# MIDI-Patchbay-Shield.net
KiCad netlist of a schematic drawn in EAGLE
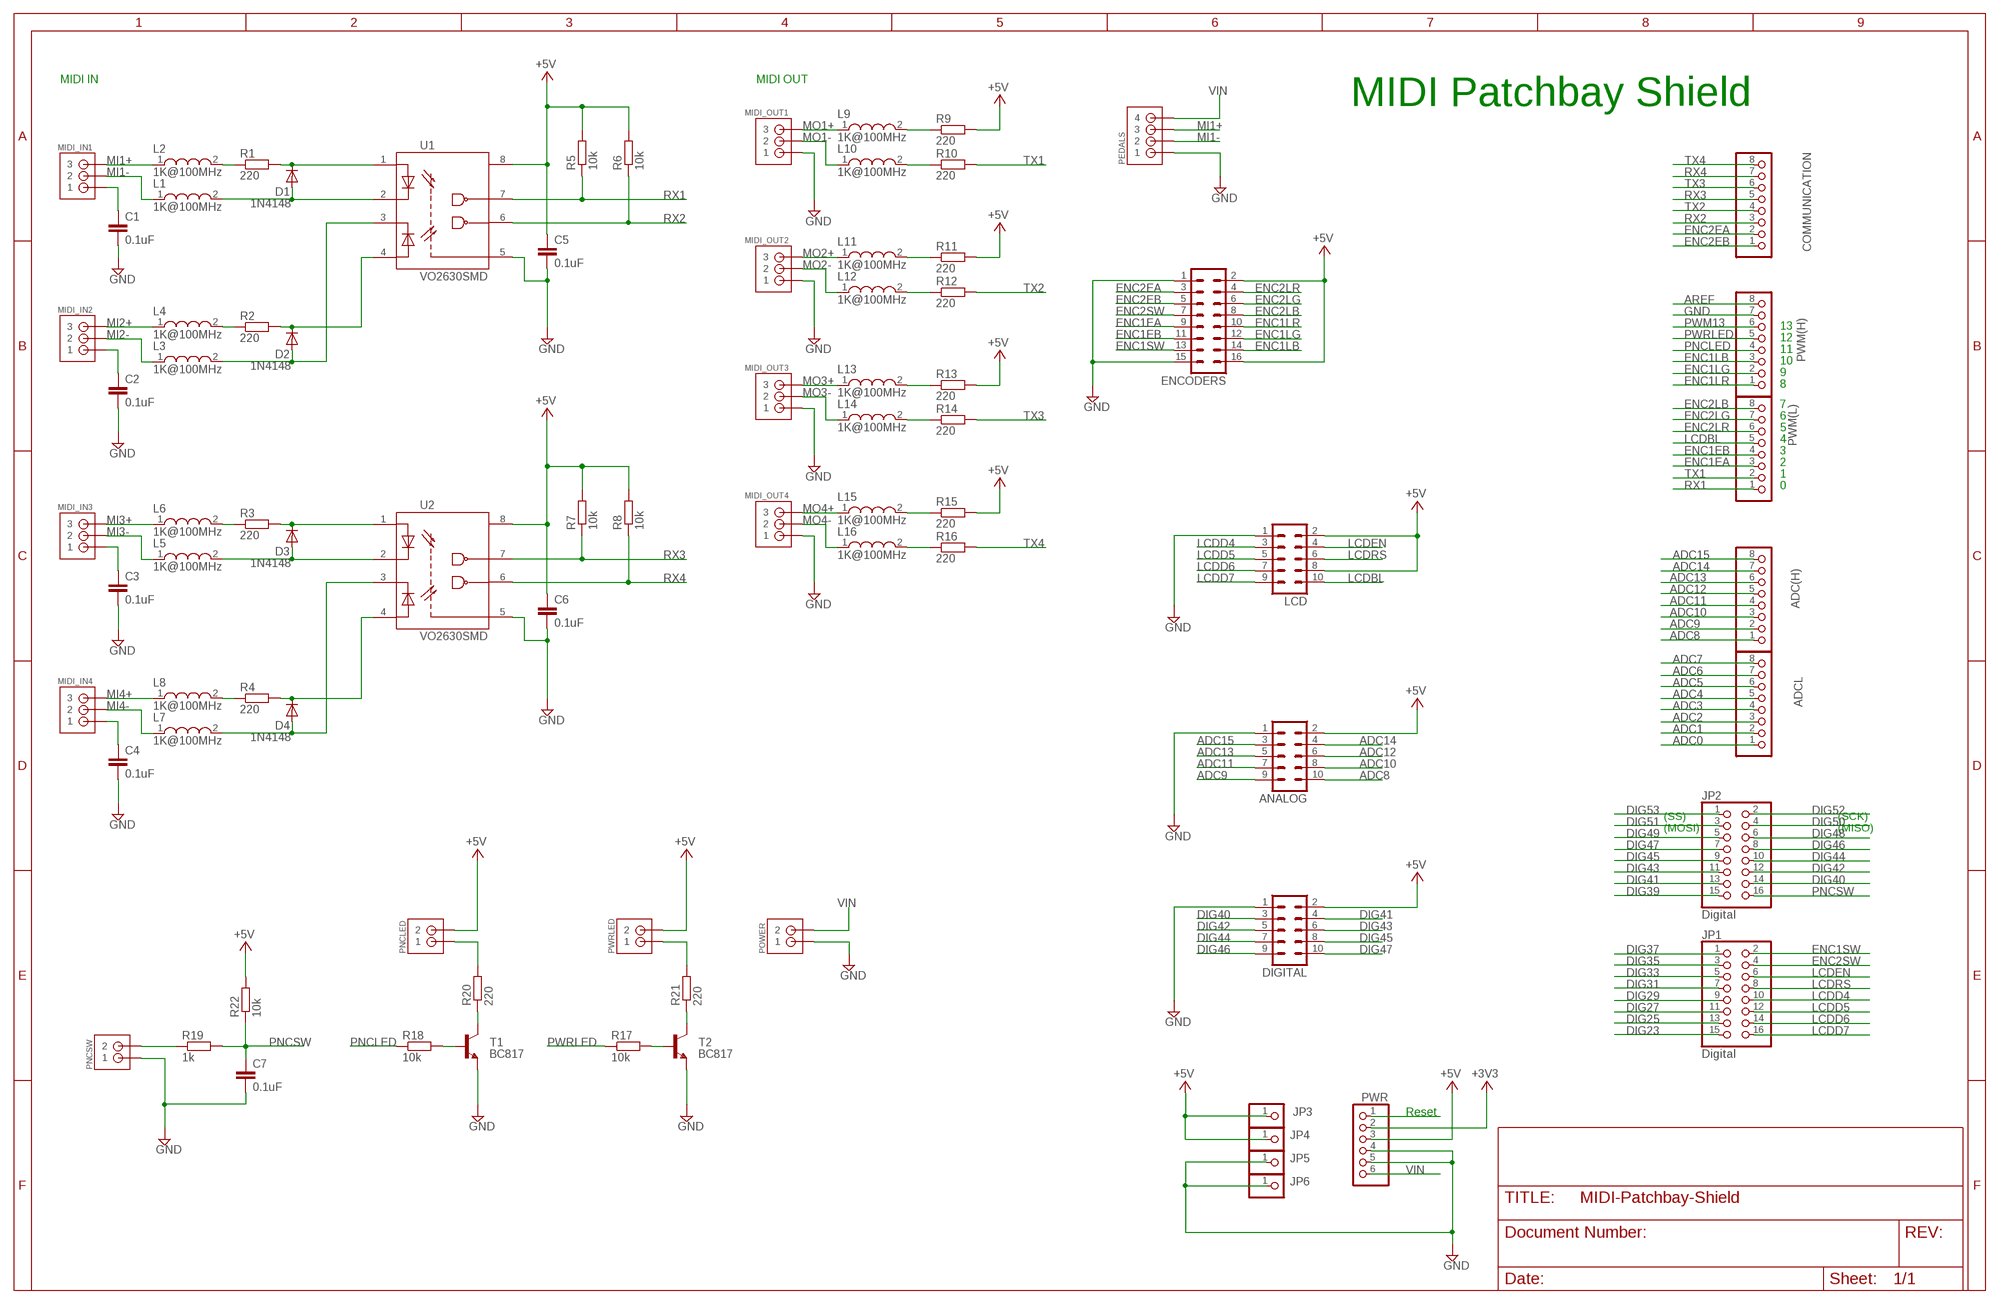
[diagram p0: schematic, sheet 1]

(export (version "E")
  (design (tool "Eeschema 10.0.6"))
  (components
    (comp (ref "ADC(H)")
      (value "PINHD-1X8")
      (footprint "eagle-import:1X08")
      (libsource (lib "eagle-import") (part "PINHD-1X8"))
    )
    (comp (ref "ADCL")
      (value "PINHD-1X8")
      (footprint "eagle-import:1X08")
      (libsource (lib "eagle-import") (part "PINHD-1X8"))
    )
    (comp (ref "ANALOG")
      (value "ML10")
      (footprint "eagle-import:ML10")
      (libsource (lib "eagle-import") (part "ML10"))
    )
    (comp (ref "C1")
      (value "0.1uF")
      (footprint "eagle-import:0805")
      (libsource (lib "eagle-import") (part "CAP0805"))
    )
    (comp (ref "C2")
      (value "0.1uF")
      (footprint "eagle-import:0805")
      (libsource (lib "eagle-import") (part "CAP0805"))
    )
    (comp (ref "C3")
      (value "0.1uF")
      (footprint "eagle-import:0805")
      (libsource (lib "eagle-import") (part "CAP0805"))
    )
    (comp (ref "C4")
      (value "0.1uF")
      (footprint "eagle-import:0805")
      (libsource (lib "eagle-import") (part "CAP0805"))
    )
    (comp (ref "C5")
      (value "0.1uF")
      (footprint "eagle-import:C0805")
      (libsource (lib "eagle-import") (part "C-EUC0805"))
    )
    (comp (ref "C6")
      (value "0.1uF")
      (footprint "eagle-import:C0805")
      (libsource (lib "eagle-import") (part "C-EUC0805"))
    )
    (comp (ref "C7")
      (value "0.1uF")
      (footprint "eagle-import:0805")
      (libsource (lib "eagle-import") (part "CAP0805"))
    )
    (comp (ref "COMMUNICATION")
      (value "PINHD-1X8")
      (footprint "eagle-import:1X08")
      (libsource (lib "eagle-import") (part "PINHD-1X8"))
    )
    (comp (ref "D1")
      (value "1N4148")
      (footprint "eagle-import:SOD323-W")
      (libsource (lib "eagle-import") (part "1N4148"))
    )
    (comp (ref "D2")
      (value "1N4148")
      (footprint "eagle-import:SOD323-W")
      (libsource (lib "eagle-import") (part "1N4148"))
    )
    (comp (ref "D3")
      (value "1N4148")
      (footprint "eagle-import:SOD323-W")
      (libsource (lib "eagle-import") (part "1N4148"))
    )
    (comp (ref "D4")
      (value "1N4148")
      (footprint "eagle-import:SOD323-W")
      (libsource (lib "eagle-import") (part "1N4148"))
    )
    (comp (ref "DIGITAL")
      (value "ML10")
      (footprint "eagle-import:ML10")
      (libsource (lib "eagle-import") (part "ML10"))
    )
    (comp (ref "ENCODERS")
      (value "ML16")
      (footprint "eagle-import:ML16")
      (libsource (lib "eagle-import") (part "ML16"))
    )
    (comp (ref "JP1")
      (value "Digital")
      (footprint "eagle-import:2X08")
      (libsource (lib "eagle-import") (part "PINHD-2X8"))
    )
    (comp (ref "JP2")
      (value "Digital")
      (footprint "eagle-import:2X08")
      (libsource (lib "eagle-import") (part "PINHD-2X8"))
    )
    (comp (ref "JP3")
      (value "PINHD-1X1")
      (footprint "eagle-import:1X01")
      (libsource (lib "eagle-import") (part "PINHD-1X1"))
    )
    (comp (ref "JP4")
      (value "PINHD-1X1")
      (footprint "eagle-import:1X01")
      (libsource (lib "eagle-import") (part "PINHD-1X1"))
    )
    (comp (ref "JP5")
      (value "PINHD-1X1")
      (footprint "eagle-import:1X01")
      (libsource (lib "eagle-import") (part "PINHD-1X1"))
    )
    (comp (ref "JP6")
      (value "PINHD-1X1")
      (footprint "eagle-import:1X01")
      (libsource (lib "eagle-import") (part "PINHD-1X1"))
    )
    (comp (ref "L1")
      (value "1K@100MHz")
      (footprint "eagle-import:WE-RFI_0805")
      (libsource (lib "eagle-import") (part "WE-RFI_0805"))
    )
    (comp (ref "L2")
      (value "1K@100MHz")
      (footprint "eagle-import:WE-RFI_0805")
      (libsource (lib "eagle-import") (part "WE-RFI_0805"))
    )
    (comp (ref "L3")
      (value "1K@100MHz")
      (footprint "eagle-import:WE-RFI_0805")
      (libsource (lib "eagle-import") (part "WE-RFI_0805"))
    )
    (comp (ref "L4")
      (value "1K@100MHz")
      (footprint "eagle-import:WE-RFI_0805")
      (libsource (lib "eagle-import") (part "WE-RFI_0805"))
    )
    (comp (ref "L5")
      (value "1K@100MHz")
      (footprint "eagle-import:WE-RFI_0805")
      (libsource (lib "eagle-import") (part "WE-RFI_0805"))
    )
    (comp (ref "L6")
      (value "1K@100MHz")
      (footprint "eagle-import:WE-RFI_0805")
      (libsource (lib "eagle-import") (part "WE-RFI_0805"))
    )
    (comp (ref "L7")
      (value "1K@100MHz")
      (footprint "eagle-import:WE-RFI_0805")
      (libsource (lib "eagle-import") (part "WE-RFI_0805"))
    )
    (comp (ref "L8")
      (value "1K@100MHz")
      (footprint "eagle-import:WE-RFI_0805")
      (libsource (lib "eagle-import") (part "WE-RFI_0805"))
    )
    (comp (ref "L9")
      (value "1K@100MHz")
      (footprint "eagle-import:WE-RFI_0805")
      (libsource (lib "eagle-import") (part "WE-RFI_0805"))
    )
    (comp (ref "L10")
      (value "1K@100MHz")
      (footprint "eagle-import:WE-RFI_0805")
      (libsource (lib "eagle-import") (part "WE-RFI_0805"))
    )
    (comp (ref "L11")
      (value "1K@100MHz")
      (footprint "eagle-import:WE-RFI_0805")
      (libsource (lib "eagle-import") (part "WE-RFI_0805"))
    )
    (comp (ref "L12")
      (value "1K@100MHz")
      (footprint "eagle-import:WE-RFI_0805")
      (libsource (lib "eagle-import") (part "WE-RFI_0805"))
    )
    (comp (ref "L13")
      (value "1K@100MHz")
      (footprint "eagle-import:WE-RFI_0805")
      (libsource (lib "eagle-import") (part "WE-RFI_0805"))
    )
    (comp (ref "L14")
      (value "1K@100MHz")
      (footprint "eagle-import:WE-RFI_0805")
      (libsource (lib "eagle-import") (part "WE-RFI_0805"))
    )
    (comp (ref "L15")
      (value "1K@100MHz")
      (footprint "eagle-import:WE-RFI_0805")
      (libsource (lib "eagle-import") (part "WE-RFI_0805"))
    )
    (comp (ref "L16")
      (value "1K@100MHz")
      (footprint "eagle-import:WE-RFI_0805")
      (libsource (lib "eagle-import") (part "WE-RFI_0805"))
    )
    (comp (ref "LCD")
      (value "ML10")
      (footprint "eagle-import:ML10")
      (libsource (lib "eagle-import") (part "ML10"))
    )
    (comp (ref "MIDI_IN1")
      (value "JST-XA-03-PIN")
      (footprint "eagle-import:JST-XA-03")
      (libsource (lib "eagle-import") (part "JST-XA-03-PIN"))
    )
    (comp (ref "MIDI_IN2")
      (value "JST-XA-03-PIN")
      (footprint "eagle-import:JST-XA-03")
      (libsource (lib "eagle-import") (part "JST-XA-03-PIN"))
    )
    (comp (ref "MIDI_IN3")
      (value "JST-XA-03-PIN")
      (footprint "eagle-import:JST-XA-03")
      (libsource (lib "eagle-import") (part "JST-XA-03-PIN"))
    )
    (comp (ref "MIDI_IN4")
      (value "JST-XA-03-PIN")
      (footprint "eagle-import:JST-XA-03")
      (libsource (lib "eagle-import") (part "JST-XA-03-PIN"))
    )
    (comp (ref "MIDI_OUT1")
      (value "JST-XA-03-PIN")
      (footprint "eagle-import:JST-XA-03")
      (libsource (lib "eagle-import") (part "JST-XA-03-PIN"))
    )
    (comp (ref "MIDI_OUT2")
      (value "JST-XA-03-PIN")
      (footprint "eagle-import:JST-XA-03")
      (libsource (lib "eagle-import") (part "JST-XA-03-PIN"))
    )
    (comp (ref "MIDI_OUT3")
      (value "JST-XA-03-PIN")
      (footprint "eagle-import:JST-XA-03")
      (libsource (lib "eagle-import") (part "JST-XA-03-PIN"))
    )
    (comp (ref "MIDI_OUT4")
      (value "JST-XA-03-PIN")
      (footprint "eagle-import:JST-XA-03")
      (libsource (lib "eagle-import") (part "JST-XA-03-PIN"))
    )
    (comp (ref "PEDALS")
      (value "JST-XA-04-PIN")
      (footprint "eagle-import:JST-XA-04")
      (libsource (lib "eagle-import") (part "JST-XA-04-PIN"))
    )
    (comp (ref "PNCLED")
      (value "JST-XA-02-PIN")
      (footprint "eagle-import:JST-XA-02")
      (libsource (lib "eagle-import") (part "JST-XA-02-PIN"))
    )
    (comp (ref "PNCSW")
      (value "JST-XA-02-PIN")
      (footprint "eagle-import:JST-XA-02")
      (libsource (lib "eagle-import") (part "JST-XA-02-PIN"))
    )
    (comp (ref "POWER")
      (value "JST-XA-02-PIN")
      (footprint "eagle-import:JST-XA-02")
      (libsource (lib "eagle-import") (part "JST-XA-02-PIN"))
    )
    (comp (ref "PWM(H)")
      (value "PINHD-1X8")
      (footprint "eagle-import:1X08")
      (libsource (lib "eagle-import") (part "PINHD-1X8"))
    )
    (comp (ref "PWM(L)")
      (value "PINHD-1X8")
      (footprint "eagle-import:1X08")
      (libsource (lib "eagle-import") (part "PINHD-1X8"))
    )
    (comp (ref "PWR")
      (value "PINHD-1X6")
      (footprint "eagle-import:1X06")
      (libsource (lib "eagle-import") (part "PINHD-1X6"))
    )
    (comp (ref "PWRLED")
      (value "JST-XA-02-PIN")
      (footprint "eagle-import:JST-XA-02")
      (libsource (lib "eagle-import") (part "JST-XA-02-PIN"))
    )
    (comp (ref "R1")
      (value "220")
      (footprint "eagle-import:M0805")
      (libsource (lib "eagle-import") (part "R-EU_M0805"))
    )
    (comp (ref "R2")
      (value "220")
      (footprint "eagle-import:M0805")
      (libsource (lib "eagle-import") (part "R-EU_M0805"))
    )
    (comp (ref "R3")
      (value "220")
      (footprint "eagle-import:M0805")
      (libsource (lib "eagle-import") (part "R-EU_M0805"))
    )
    (comp (ref "R4")
      (value "220")
      (footprint "eagle-import:M0805")
      (libsource (lib "eagle-import") (part "R-EU_M0805"))
    )
    (comp (ref "R5")
      (value "10k")
      (footprint "eagle-import:R0805")
      (libsource (lib "eagle-import") (part "R-EU_R0805"))
    )
    (comp (ref "R6")
      (value "10k")
      (footprint "eagle-import:R0805")
      (libsource (lib "eagle-import") (part "R-EU_R0805"))
    )
    (comp (ref "R7")
      (value "10k")
      (footprint "eagle-import:R0805")
      (libsource (lib "eagle-import") (part "R-EU_R0805"))
    )
    (comp (ref "R8")
      (value "10k")
      (footprint "eagle-import:R0805")
      (libsource (lib "eagle-import") (part "R-EU_R0805"))
    )
    (comp (ref "R9")
      (value "220")
      (footprint "eagle-import:M0805")
      (libsource (lib "eagle-import") (part "R-EU_M0805"))
    )
    (comp (ref "R10")
      (value "220")
      (footprint "eagle-import:M0805")
      (libsource (lib "eagle-import") (part "R-EU_M0805"))
    )
    (comp (ref "R11")
      (value "220")
      (footprint "eagle-import:M0805")
      (libsource (lib "eagle-import") (part "R-EU_M0805"))
    )
    (comp (ref "R12")
      (value "220")
      (footprint "eagle-import:M0805")
      (libsource (lib "eagle-import") (part "R-EU_M0805"))
    )
    (comp (ref "R13")
      (value "220")
      (footprint "eagle-import:M0805")
      (libsource (lib "eagle-import") (part "R-EU_M0805"))
    )
    (comp (ref "R14")
      (value "220")
      (footprint "eagle-import:M0805")
      (libsource (lib "eagle-import") (part "R-EU_M0805"))
    )
    (comp (ref "R15")
      (value "220")
      (footprint "eagle-import:M0805")
      (libsource (lib "eagle-import") (part "R-EU_M0805"))
    )
    (comp (ref "R16")
      (value "220")
      (footprint "eagle-import:M0805")
      (libsource (lib "eagle-import") (part "R-EU_M0805"))
    )
    (comp (ref "R17")
      (value "10k")
      (footprint "eagle-import:R0805")
      (fields (field (name "SPICEPREFIX") "R"))
      (libsource (lib "eagle-import") (part "R-EU_R0805"))
    )
    (comp (ref "R18")
      (value "10k")
      (footprint "eagle-import:R0805")
      (fields (field (name "SPICEPREFIX") "R"))
      (libsource (lib "eagle-import") (part "R-EU_R0805"))
    )
    (comp (ref "R19")
      (value "1k")
      (footprint "eagle-import:R0805")
      (fields (field (name "SPICEPREFIX") "R"))
      (libsource (lib "eagle-import") (part "R-EU_R0805"))
    )
    (comp (ref "R20")
      (value "220")
      (footprint "eagle-import:M0805")
      (libsource (lib "eagle-import") (part "R-EU_M0805"))
    )
    (comp (ref "R21")
      (value "220")
      (footprint "eagle-import:M0805")
      (libsource (lib "eagle-import") (part "R-EU_M0805"))
    )
    (comp (ref "R22")
      (value "10k")
      (footprint "eagle-import:R0805")
      (fields (field (name "SPICEPREFIX") "R"))
      (libsource (lib "eagle-import") (part "R-EU_R0805"))
    )
    (comp (ref "T1")
      (value "BC817")
      (footprint "eagle-import:SOT23")
      (libsource (lib "eagle-import") (part "BC817"))
    )
    (comp (ref "T2")
      (value "BC817")
      (footprint "eagle-import:SOT23")
      (libsource (lib "eagle-import") (part "BC817"))
    )
    (comp (ref "U1")
      (value "VO2630SMD")
      (footprint "eagle-import:SOIC254P1030X390-8N")
      (libsource (lib "eagle-import") (part "VO2630SMD"))
    )
    (comp (ref "U2")
      (value "VO2630SMD")
      (footprint "eagle-import:SOIC254P1030X390-8N")
      (libsource (lib "eagle-import") (part "VO2630SMD"))
    )
  )
  (nets
    (net (code "1") (name "+3V3") (class "Default")
      (node (ref "PWR") (pin "2") (pinfunction "2_2") (pintype "passive"))
    )
    (net (code "2") (name "+5V") (class "Default")
      (node (ref "ANALOG") (pin "2") (pinfunction "2_2") (pintype "passive"))
      (node (ref "C5") (pin "1") (pinfunction "1_1") (pintype "passive"))
      (node (ref "C6") (pin "1") (pinfunction "1_1") (pintype "passive"))
      (node (ref "DIGITAL") (pin "2") (pinfunction "2_2") (pintype "passive"))
      (node (ref "ENCODERS") (pin "16") (pinfunction "16_16") (pintype "passive"))
      (node (ref "ENCODERS") (pin "2") (pinfunction "2_2") (pintype "passive"))
      (node (ref "JP3") (pin "1") (pinfunction "1_1") (pintype "passive"))
      (node (ref "JP4") (pin "1") (pinfunction "1_1") (pintype "passive"))
      (node (ref "LCD") (pin "2") (pinfunction "2_2") (pintype "passive"))
      (node (ref "LCD") (pin "8") (pinfunction "8_8") (pintype "passive"))
      (node (ref "PNCLED") (pin "2") (pinfunction "2_2") (pintype "bidirectional"))
      (node (ref "PWR") (pin "3") (pinfunction "3_3") (pintype "passive"))
      (node (ref "PWRLED") (pin "2") (pinfunction "2_2") (pintype "bidirectional"))
      (node (ref "R11") (pin "2") (pinfunction "2_2") (pintype "passive"))
      (node (ref "R13") (pin "2") (pinfunction "2_2") (pintype "passive"))
      (node (ref "R15") (pin "2") (pinfunction "2_2") (pintype "passive"))
      (node (ref "R22") (pin "2") (pinfunction "2_2") (pintype "passive"))
      (node (ref "R5") (pin "2") (pinfunction "2_2") (pintype "passive"))
      (node (ref "R6") (pin "2") (pinfunction "2_2") (pintype "passive"))
      (node (ref "R7") (pin "2") (pinfunction "2_2") (pintype "passive"))
      (node (ref "R8") (pin "2") (pinfunction "2_2") (pintype "passive"))
      (node (ref "R9") (pin "2") (pinfunction "2_2") (pintype "passive"))
      (node (ref "U1") (pin "8") (pinfunction "VCC_8") (pintype "power_in"))
      (node (ref "U2") (pin "8") (pinfunction "VCC_8") (pintype "power_in"))
    )
    (net (code "3") (name "/ADC0") (class "Default")
      (node (ref "ADCL") (pin "1") (pinfunction "1_1") (pintype "passive"))
    )
    (net (code "4") (name "/ADC1") (class "Default")
      (node (ref "ADCL") (pin "2") (pinfunction "2_2") (pintype "passive"))
    )
    (net (code "5") (name "/ADC2") (class "Default")
      (node (ref "ADCL") (pin "3") (pinfunction "3_3") (pintype "passive"))
    )
    (net (code "6") (name "/ADC3") (class "Default")
      (node (ref "ADCL") (pin "4") (pinfunction "4_4") (pintype "passive"))
    )
    (net (code "7") (name "/ADC4") (class "Default")
      (node (ref "ADCL") (pin "5") (pinfunction "5_5") (pintype "passive"))
    )
    (net (code "8") (name "/ADC5") (class "Default")
      (node (ref "ADCL") (pin "6") (pinfunction "6_6") (pintype "passive"))
    )
    (net (code "9") (name "/ADC6") (class "Default")
      (node (ref "ADCL") (pin "7") (pinfunction "7_7") (pintype "passive"))
    )
    (net (code "10") (name "/ADC7") (class "Default")
      (node (ref "ADCL") (pin "8") (pinfunction "8_8") (pintype "passive"))
    )
    (net (code "11") (name "/ADC8") (class "Default")
      (node (ref "ADC(H)") (pin "1") (pinfunction "1_1") (pintype "passive"))
      (node (ref "ANALOG") (pin "10") (pinfunction "10_10") (pintype "passive"))
    )
    (net (code "12") (name "/ADC9") (class "Default")
      (node (ref "ADC(H)") (pin "2") (pinfunction "2_2") (pintype "passive"))
      (node (ref "ANALOG") (pin "9") (pinfunction "9_9") (pintype "passive"))
    )
    (net (code "13") (name "/ADC10") (class "Default")
      (node (ref "ADC(H)") (pin "3") (pinfunction "3_3") (pintype "passive"))
      (node (ref "ANALOG") (pin "8") (pinfunction "8_8") (pintype "passive"))
    )
    (net (code "14") (name "/ADC11") (class "Default")
      (node (ref "ADC(H)") (pin "4") (pinfunction "4_4") (pintype "passive"))
      (node (ref "ANALOG") (pin "7") (pinfunction "7_7") (pintype "passive"))
    )
    (net (code "15") (name "/ADC12") (class "Default")
      (node (ref "ADC(H)") (pin "5") (pinfunction "5_5") (pintype "passive"))
      (node (ref "ANALOG") (pin "6") (pinfunction "6_6") (pintype "passive"))
    )
    (net (code "16") (name "/ADC13") (class "Default")
      (node (ref "ADC(H)") (pin "6") (pinfunction "6_6") (pintype "passive"))
      (node (ref "ANALOG") (pin "5") (pinfunction "5_5") (pintype "passive"))
    )
    (net (code "17") (name "/ADC14") (class "Default")
      (node (ref "ADC(H)") (pin "7") (pinfunction "7_7") (pintype "passive"))
      (node (ref "ANALOG") (pin "4") (pinfunction "4_4") (pintype "passive"))
    )
    (net (code "18") (name "/ADC15") (class "Default")
      (node (ref "ADC(H)") (pin "8") (pinfunction "8_8") (pintype "passive"))
      (node (ref "ANALOG") (pin "3") (pinfunction "3_3") (pintype "passive"))
    )
    (net (code "19") (name "/AREF") (class "Default")
      (node (ref "PWM(H)") (pin "8") (pinfunction "8_8") (pintype "passive"))
    )
    (net (code "20") (name "/DIG23") (class "Default")
      (node (ref "JP1") (pin "15") (pinfunction "15_15") (pintype "passive"))
    )
    (net (code "21") (name "/DIG25") (class "Default")
      (node (ref "JP1") (pin "13") (pinfunction "13_13") (pintype "passive"))
    )
    (net (code "22") (name "/DIG27") (class "Default")
      (node (ref "JP1") (pin "11") (pinfunction "11_11") (pintype "passive"))
    )
    (net (code "23") (name "/DIG29") (class "Default")
      (node (ref "JP1") (pin "9") (pinfunction "9_9") (pintype "passive"))
    )
    (net (code "24") (name "/DIG31") (class "Default")
      (node (ref "JP1") (pin "7") (pinfunction "7_7") (pintype "passive"))
    )
    (net (code "25") (name "/DIG33") (class "Default")
      (node (ref "JP1") (pin "5") (pinfunction "5_5") (pintype "passive"))
    )
    (net (code "26") (name "/DIG35") (class "Default")
      (node (ref "JP1") (pin "3") (pinfunction "3_3") (pintype "passive"))
    )
    (net (code "27") (name "/DIG37") (class "Default")
      (node (ref "JP1") (pin "1") (pinfunction "1_1") (pintype "passive"))
    )
    (net (code "28") (name "/DIG39") (class "Default")
      (node (ref "JP2") (pin "15") (pinfunction "15_15") (pintype "passive"))
    )
    (net (code "29") (name "/DIG40") (class "Default")
      (node (ref "DIGITAL") (pin "3") (pinfunction "3_3") (pintype "passive"))
      (node (ref "JP2") (pin "14") (pinfunction "14_14") (pintype "passive"))
    )
    (net (code "30") (name "/DIG41") (class "Default")
      (node (ref "DIGITAL") (pin "4") (pinfunction "4_4") (pintype "passive"))
      (node (ref "JP2") (pin "13") (pinfunction "13_13") (pintype "passive"))
    )
    (net (code "31") (name "/DIG42") (class "Default")
      (node (ref "DIGITAL") (pin "5") (pinfunction "5_5") (pintype "passive"))
      (node (ref "JP2") (pin "12") (pinfunction "12_12") (pintype "passive"))
    )
    (net (code "32") (name "/DIG43") (class "Default")
      (node (ref "DIGITAL") (pin "6") (pinfunction "6_6") (pintype "passive"))
      (node (ref "JP2") (pin "11") (pinfunction "11_11") (pintype "passive"))
    )
    (net (code "33") (name "/DIG44") (class "Default")
      (node (ref "DIGITAL") (pin "7") (pinfunction "7_7") (pintype "passive"))
      (node (ref "JP2") (pin "10") (pinfunction "10_10") (pintype "passive"))
    )
    (net (code "34") (name "/DIG45") (class "Default")
      (node (ref "DIGITAL") (pin "8") (pinfunction "8_8") (pintype "passive"))
      (node (ref "JP2") (pin "9") (pinfunction "9_9") (pintype "passive"))
    )
    (net (code "35") (name "/DIG46") (class "Default")
      (node (ref "DIGITAL") (pin "9") (pinfunction "9_9") (pintype "passive"))
      (node (ref "JP2") (pin "8") (pinfunction "8_8") (pintype "passive"))
    )
    (net (code "36") (name "/DIG47") (class "Default")
      (node (ref "DIGITAL") (pin "10") (pinfunction "10_10") (pintype "passive"))
      (node (ref "JP2") (pin "7") (pinfunction "7_7") (pintype "passive"))
    )
    (net (code "37") (name "/DIG48") (class "Default")
      (node (ref "JP2") (pin "6") (pinfunction "6_6") (pintype "passive"))
    )
    (net (code "38") (name "/DIG49") (class "Default")
      (node (ref "JP2") (pin "5") (pinfunction "5_5") (pintype "passive"))
    )
    (net (code "39") (name "/DIG50") (class "Default")
      (node (ref "JP2") (pin "4") (pinfunction "4_4") (pintype "passive"))
    )
    (net (code "40") (name "/DIG51") (class "Default")
      (node (ref "JP2") (pin "3") (pinfunction "3_3") (pintype "passive"))
    )
    (net (code "41") (name "/DIG52") (class "Default")
      (node (ref "JP2") (pin "2") (pinfunction "2_2") (pintype "passive"))
    )
    (net (code "42") (name "/DIG53") (class "Default")
      (node (ref "JP2") (pin "1") (pinfunction "1_1") (pintype "passive"))
    )
    (net (code "43") (name "/ENC1EA") (class "Default")
      (node (ref "ENCODERS") (pin "9") (pinfunction "9_9") (pintype "passive"))
      (node (ref "PWM(L)") (pin "3") (pinfunction "3_3") (pintype "passive"))
    )
    (net (code "44") (name "/ENC1EB") (class "Default")
      (node (ref "ENCODERS") (pin "11") (pinfunction "11_11") (pintype "passive"))
      (node (ref "PWM(L)") (pin "4") (pinfunction "4_4") (pintype "passive"))
    )
    (net (code "45") (name "/ENC1LB") (class "Default")
      (node (ref "ENCODERS") (pin "14") (pinfunction "14_14") (pintype "passive"))
      (node (ref "PWM(H)") (pin "3") (pinfunction "3_3") (pintype "passive"))
    )
    (net (code "46") (name "/ENC1LG") (class "Default")
      (node (ref "ENCODERS") (pin "12") (pinfunction "12_12") (pintype "passive"))
      (node (ref "PWM(H)") (pin "2") (pinfunction "2_2") (pintype "passive"))
    )
    (net (code "47") (name "/ENC1LR") (class "Default")
      (node (ref "ENCODERS") (pin "10") (pinfunction "10_10") (pintype "passive"))
      (node (ref "PWM(H)") (pin "1") (pinfunction "1_1") (pintype "passive"))
    )
    (net (code "48") (name "/ENC1SW") (class "Default")
      (node (ref "ENCODERS") (pin "13") (pinfunction "13_13") (pintype "passive"))
      (node (ref "JP1") (pin "2") (pinfunction "2_2") (pintype "passive"))
    )
    (net (code "49") (name "/ENC2EA") (class "Default")
      (node (ref "COMMUNICATION") (pin "2") (pinfunction "2_2") (pintype "passive"))
      (node (ref "ENCODERS") (pin "3") (pinfunction "3_3") (pintype "passive"))
    )
    (net (code "50") (name "/ENC2EB") (class "Default")
      (node (ref "COMMUNICATION") (pin "1") (pinfunction "1_1") (pintype "passive"))
      (node (ref "ENCODERS") (pin "5") (pinfunction "5_5") (pintype "passive"))
    )
    (net (code "51") (name "/ENC2LB") (class "Default")
      (node (ref "ENCODERS") (pin "8") (pinfunction "8_8") (pintype "passive"))
      (node (ref "PWM(L)") (pin "8") (pinfunction "8_8") (pintype "passive"))
    )
    (net (code "52") (name "/ENC2LG") (class "Default")
      (node (ref "ENCODERS") (pin "6") (pinfunction "6_6") (pintype "passive"))
      (node (ref "PWM(L)") (pin "7") (pinfunction "7_7") (pintype "passive"))
    )
    (net (code "53") (name "/ENC2LR") (class "Default")
      (node (ref "ENCODERS") (pin "4") (pinfunction "4_4") (pintype "passive"))
      (node (ref "PWM(L)") (pin "6") (pinfunction "6_6") (pintype "passive"))
    )
    (net (code "54") (name "/ENC2SW") (class "Default")
      (node (ref "ENCODERS") (pin "7") (pinfunction "7_7") (pintype "passive"))
      (node (ref "JP1") (pin "4") (pinfunction "4_4") (pintype "passive"))
    )
    (net (code "55") (name "/LCDBL") (class "Default")
      (node (ref "LCD") (pin "10") (pinfunction "10_10") (pintype "passive"))
      (node (ref "PWM(L)") (pin "5") (pinfunction "5_5") (pintype "passive"))
    )
    (net (code "56") (name "/LCDD4") (class "Default")
      (node (ref "JP1") (pin "10") (pinfunction "10_10") (pintype "passive"))
      (node (ref "LCD") (pin "3") (pinfunction "3_3") (pintype "passive"))
    )
    (net (code "57") (name "/LCDD5") (class "Default")
      (node (ref "JP1") (pin "12") (pinfunction "12_12") (pintype "passive"))
      (node (ref "LCD") (pin "5") (pinfunction "5_5") (pintype "passive"))
    )
    (net (code "58") (name "/LCDD6") (class "Default")
      (node (ref "JP1") (pin "14") (pinfunction "14_14") (pintype "passive"))
      (node (ref "LCD") (pin "7") (pinfunction "7_7") (pintype "passive"))
    )
    (net (code "59") (name "/LCDD7") (class "Default")
      (node (ref "JP1") (pin "16") (pinfunction "16_16") (pintype "passive"))
      (node (ref "LCD") (pin "9") (pinfunction "9_9") (pintype "passive"))
    )
    (net (code "60") (name "/LCDEN") (class "Default")
      (node (ref "JP1") (pin "6") (pinfunction "6_6") (pintype "passive"))
      (node (ref "LCD") (pin "4") (pinfunction "4_4") (pintype "passive"))
    )
    (net (code "61") (name "/LCDRS") (class "Default")
      (node (ref "JP1") (pin "8") (pinfunction "8_8") (pintype "passive"))
      (node (ref "LCD") (pin "6") (pinfunction "6_6") (pintype "passive"))
    )
    (net (code "62") (name "/MI1+") (class "Default")
      (node (ref "L2") (pin "1") (pinfunction "1_1") (pintype "passive"))
      (node (ref "MIDI_IN1") (pin "3") (pinfunction "3_3") (pintype "bidirectional"))
      (node (ref "PEDALS") (pin "3") (pinfunction "3_3") (pintype "bidirectional"))
    )
    (net (code "63") (name "/MI1-") (class "Default")
      (node (ref "L1") (pin "1") (pinfunction "1_1") (pintype "passive"))
      (node (ref "MIDI_IN1") (pin "2") (pinfunction "2_2") (pintype "bidirectional"))
      (node (ref "PEDALS") (pin "2") (pinfunction "2_2") (pintype "bidirectional"))
    )
    (net (code "64") (name "/MI2+") (class "Default")
      (node (ref "L4") (pin "1") (pinfunction "1_1") (pintype "passive"))
      (node (ref "MIDI_IN2") (pin "3") (pinfunction "3_3") (pintype "bidirectional"))
    )
    (net (code "65") (name "/MI2-") (class "Default")
      (node (ref "L3") (pin "1") (pinfunction "1_1") (pintype "passive"))
      (node (ref "MIDI_IN2") (pin "2") (pinfunction "2_2") (pintype "bidirectional"))
    )
    (net (code "66") (name "/MI3+") (class "Default")
      (node (ref "L6") (pin "1") (pinfunction "1_1") (pintype "passive"))
      (node (ref "MIDI_IN3") (pin "3") (pinfunction "3_3") (pintype "bidirectional"))
    )
    (net (code "67") (name "/MI3-") (class "Default")
      (node (ref "L5") (pin "1") (pinfunction "1_1") (pintype "passive"))
      (node (ref "MIDI_IN3") (pin "2") (pinfunction "2_2") (pintype "bidirectional"))
    )
    (net (code "68") (name "/MI4+") (class "Default")
      (node (ref "L8") (pin "1") (pinfunction "1_1") (pintype "passive"))
      (node (ref "MIDI_IN4") (pin "3") (pinfunction "3_3") (pintype "bidirectional"))
    )
    (net (code "69") (name "/MI4-") (class "Default")
      (node (ref "L7") (pin "1") (pinfunction "1_1") (pintype "passive"))
      (node (ref "MIDI_IN4") (pin "2") (pinfunction "2_2") (pintype "bidirectional"))
    )
    (net (code "70") (name "/MO1+") (class "Default")
      (node (ref "L9") (pin "1") (pinfunction "1_1") (pintype "passive"))
      (node (ref "MIDI_OUT1") (pin "3") (pinfunction "3_3") (pintype "bidirectional"))
    )
    (net (code "71") (name "/MO1-") (class "Default")
      (node (ref "L10") (pin "1") (pinfunction "1_1") (pintype "passive"))
      (node (ref "MIDI_OUT1") (pin "2") (pinfunction "2_2") (pintype "bidirectional"))
    )
    (net (code "72") (name "/MO2+") (class "Default")
      (node (ref "L11") (pin "1") (pinfunction "1_1") (pintype "passive"))
      (node (ref "MIDI_OUT2") (pin "3") (pinfunction "3_3") (pintype "bidirectional"))
    )
    (net (code "73") (name "/MO2-") (class "Default")
      (node (ref "L12") (pin "1") (pinfunction "1_1") (pintype "passive"))
      (node (ref "MIDI_OUT2") (pin "2") (pinfunction "2_2") (pintype "bidirectional"))
    )
    (net (code "74") (name "/MO3+") (class "Default")
      (node (ref "L13") (pin "1") (pinfunction "1_1") (pintype "passive"))
      (node (ref "MIDI_OUT3") (pin "3") (pinfunction "3_3") (pintype "bidirectional"))
    )
    (net (code "75") (name "/MO3-") (class "Default")
      (node (ref "L14") (pin "1") (pinfunction "1_1") (pintype "passive"))
      (node (ref "MIDI_OUT3") (pin "2") (pinfunction "2_2") (pintype "bidirectional"))
    )
    (net (code "76") (name "/MO4+") (class "Default")
      (node (ref "L15") (pin "1") (pinfunction "1_1") (pintype "passive"))
      (node (ref "MIDI_OUT4") (pin "3") (pinfunction "3_3") (pintype "bidirectional"))
    )
    (net (code "77") (name "/MO4-") (class "Default")
      (node (ref "L16") (pin "1") (pinfunction "1_1") (pintype "passive"))
      (node (ref "MIDI_OUT4") (pin "2") (pinfunction "2_2") (pintype "bidirectional"))
    )
    (net (code "78") (name "/PNCLED") (class "Default")
      (node (ref "PWM(H)") (pin "4") (pinfunction "4_4") (pintype "passive"))
      (node (ref "R18") (pin "1") (pinfunction "1_1") (pintype "passive"))
    )
    (net (code "79") (name "/PNCSW") (class "Default")
      (node (ref "C7") (pin "1") (pinfunction "1_1") (pintype "passive"))
      (node (ref "JP2") (pin "16") (pinfunction "16_16") (pintype "passive"))
      (node (ref "R19") (pin "2") (pinfunction "2_2") (pintype "passive"))
      (node (ref "R22") (pin "1") (pinfunction "1_1") (pintype "passive"))
    )
    (net (code "80") (name "/PWM13") (class "Default")
      (node (ref "PWM(H)") (pin "6") (pinfunction "6_6") (pintype "passive"))
    )
    (net (code "81") (name "/PWRLED") (class "Default")
      (node (ref "PWM(H)") (pin "5") (pinfunction "5_5") (pintype "passive"))
      (node (ref "R17") (pin "1") (pinfunction "1_1") (pintype "passive"))
    )
    (net (code "82") (name "/RX1") (class "Default")
      (node (ref "PWM(L)") (pin "1") (pinfunction "1_1") (pintype "passive"))
      (node (ref "R5") (pin "1") (pinfunction "1_1") (pintype "passive"))
      (node (ref "U1") (pin "7") (pinfunction "VO1_7") (pintype "passive"))
    )
    (net (code "83") (name "/RX2") (class "Default")
      (node (ref "COMMUNICATION") (pin "3") (pinfunction "3_3") (pintype "passive"))
      (node (ref "R6") (pin "1") (pinfunction "1_1") (pintype "passive"))
      (node (ref "U1") (pin "6") (pinfunction "VO2_6") (pintype "passive"))
    )
    (net (code "84") (name "/RX3") (class "Default")
      (node (ref "COMMUNICATION") (pin "5") (pinfunction "5_5") (pintype "passive"))
      (node (ref "R7") (pin "1") (pinfunction "1_1") (pintype "passive"))
      (node (ref "U2") (pin "7") (pinfunction "VO1_7") (pintype "passive"))
    )
    (net (code "85") (name "/RX4") (class "Default")
      (node (ref "COMMUNICATION") (pin "7") (pinfunction "7_7") (pintype "passive"))
      (node (ref "R8") (pin "1") (pinfunction "1_1") (pintype "passive"))
      (node (ref "U2") (pin "6") (pinfunction "VO2_6") (pintype "passive"))
    )
    (net (code "86") (name "/TX1") (class "Default")
      (node (ref "PWM(L)") (pin "2") (pinfunction "2_2") (pintype "passive"))
      (node (ref "R10") (pin "2") (pinfunction "2_2") (pintype "passive"))
    )
    (net (code "87") (name "/TX2") (class "Default")
      (node (ref "COMMUNICATION") (pin "4") (pinfunction "4_4") (pintype "passive"))
      (node (ref "R12") (pin "2") (pinfunction "2_2") (pintype "passive"))
    )
    (net (code "88") (name "/TX3") (class "Default")
      (node (ref "COMMUNICATION") (pin "6") (pinfunction "6_6") (pintype "passive"))
      (node (ref "R14") (pin "2") (pinfunction "2_2") (pintype "passive"))
    )
    (net (code "89") (name "/TX4") (class "Default")
      (node (ref "COMMUNICATION") (pin "8") (pinfunction "8_8") (pintype "passive"))
      (node (ref "R16") (pin "2") (pinfunction "2_2") (pintype "passive"))
    )
    (net (code "90") (name "/VIN") (class "Default")
      (node (ref "PEDALS") (pin "4") (pinfunction "4_4") (pintype "bidirectional"))
      (node (ref "POWER") (pin "2") (pinfunction "2_2") (pintype "bidirectional"))
      (node (ref "PWR") (pin "6") (pinfunction "6_6") (pintype "passive"))
    )
    (net (code "91") (name "GND") (class "Default")
      (node (ref "ANALOG") (pin "1") (pinfunction "1_1") (pintype "passive"))
      (node (ref "C1") (pin "2") (pinfunction "2_2") (pintype "passive"))
      (node (ref "C2") (pin "2") (pinfunction "2_2") (pintype "passive"))
      (node (ref "C3") (pin "2") (pinfunction "2_2") (pintype "passive"))
      (node (ref "C4") (pin "2") (pinfunction "2_2") (pintype "passive"))
      (node (ref "C5") (pin "2") (pinfunction "2_2") (pintype "passive"))
      (node (ref "C6") (pin "2") (pinfunction "2_2") (pintype "passive"))
      (node (ref "C7") (pin "2") (pinfunction "2_2") (pintype "passive"))
      (node (ref "DIGITAL") (pin "1") (pinfunction "1_1") (pintype "passive"))
      (node (ref "ENCODERS") (pin "1") (pinfunction "1_1") (pintype "passive"))
      (node (ref "ENCODERS") (pin "15") (pinfunction "15_15") (pintype "passive"))
      (node (ref "JP5") (pin "1") (pinfunction "1_1") (pintype "passive"))
      (node (ref "JP6") (pin "1") (pinfunction "1_1") (pintype "passive"))
      (node (ref "LCD") (pin "1") (pinfunction "1_1") (pintype "passive"))
      (node (ref "MIDI_OUT1") (pin "1") (pinfunction "1_1") (pintype "bidirectional"))
      (node (ref "MIDI_OUT2") (pin "1") (pinfunction "1_1") (pintype "bidirectional"))
      (node (ref "MIDI_OUT3") (pin "1") (pinfunction "1_1") (pintype "bidirectional"))
      (node (ref "MIDI_OUT4") (pin "1") (pinfunction "1_1") (pintype "bidirectional"))
      (node (ref "PEDALS") (pin "1") (pinfunction "1_1") (pintype "bidirectional"))
      (node (ref "PNCSW") (pin "1") (pinfunction "1_1") (pintype "bidirectional"))
      (node (ref "POWER") (pin "1") (pinfunction "1_1") (pintype "bidirectional"))
      (node (ref "PWM(H)") (pin "7") (pinfunction "7_7") (pintype "passive"))
      (node (ref "PWR") (pin "4") (pinfunction "4_4") (pintype "passive"))
      (node (ref "PWR") (pin "5") (pinfunction "5_5") (pintype "passive"))
      (node (ref "T1") (pin "2") (pinfunction "E_2") (pintype "passive"))
      (node (ref "T2") (pin "2") (pinfunction "E_2") (pintype "passive"))
      (node (ref "U1") (pin "5") (pinfunction "GND_5") (pintype "power_in"))
      (node (ref "U2") (pin "5") (pinfunction "GND_5") (pintype "power_in"))
    )
    (net (code "92") (name "Net-(C1-Pad1)") (class "Default")
      (node (ref "C1") (pin "1") (pinfunction "1_1") (pintype "passive"))
      (node (ref "MIDI_IN1") (pin "1") (pinfunction "1_1") (pintype "bidirectional"))
    )
    (net (code "93") (name "Net-(C2-Pad1)") (class "Default")
      (node (ref "C2") (pin "1") (pinfunction "1_1") (pintype "passive"))
      (node (ref "MIDI_IN2") (pin "1") (pinfunction "1_1") (pintype "bidirectional"))
    )
    (net (code "94") (name "Net-(C3-Pad1)") (class "Default")
      (node (ref "C3") (pin "1") (pinfunction "1_1") (pintype "passive"))
      (node (ref "MIDI_IN3") (pin "1") (pinfunction "1_1") (pintype "bidirectional"))
    )
    (net (code "95") (name "Net-(C4-Pad1)") (class "Default")
      (node (ref "C4") (pin "1") (pinfunction "1_1") (pintype "passive"))
      (node (ref "MIDI_IN4") (pin "1") (pinfunction "1_1") (pintype "bidirectional"))
    )
    (net (code "96") (name "Net-(L2-Pad2)") (class "Default")
      (node (ref "L2") (pin "2") (pinfunction "2_2") (pintype "passive"))
      (node (ref "R1") (pin "1") (pinfunction "1_1") (pintype "passive"))
    )
    (net (code "97") (name "Net-(L4-Pad2)") (class "Default")
      (node (ref "L4") (pin "2") (pinfunction "2_2") (pintype "passive"))
      (node (ref "R2") (pin "1") (pinfunction "1_1") (pintype "passive"))
    )
    (net (code "98") (name "Net-(L6-Pad2)") (class "Default")
      (node (ref "L6") (pin "2") (pinfunction "2_2") (pintype "passive"))
      (node (ref "R3") (pin "1") (pinfunction "1_1") (pintype "passive"))
    )
    (net (code "99") (name "Net-(L8-Pad2)") (class "Default")
      (node (ref "L8") (pin "2") (pinfunction "2_2") (pintype "passive"))
      (node (ref "R4") (pin "1") (pinfunction "1_1") (pintype "passive"))
    )
    (net (code "100") (name "Net-(L9-Pad2)") (class "Default")
      (node (ref "L9") (pin "2") (pinfunction "2_2") (pintype "passive"))
      (node (ref "R9") (pin "1") (pinfunction "1_1") (pintype "passive"))
    )
    (net (code "101") (name "Net-(L10-Pad2)") (class "Default")
      (node (ref "L10") (pin "2") (pinfunction "2_2") (pintype "passive"))
      (node (ref "R10") (pin "1") (pinfunction "1_1") (pintype "passive"))
    )
    (net (code "102") (name "Net-(L11-Pad2)") (class "Default")
      (node (ref "L11") (pin "2") (pinfunction "2_2") (pintype "passive"))
      (node (ref "R11") (pin "1") (pinfunction "1_1") (pintype "passive"))
    )
    (net (code "103") (name "Net-(L12-Pad2)") (class "Default")
      (node (ref "L12") (pin "2") (pinfunction "2_2") (pintype "passive"))
      (node (ref "R12") (pin "1") (pinfunction "1_1") (pintype "passive"))
    )
    (net (code "104") (name "Net-(L13-Pad2)") (class "Default")
      (node (ref "L13") (pin "2") (pinfunction "2_2") (pintype "passive"))
      (node (ref "R13") (pin "1") (pinfunction "1_1") (pintype "passive"))
    )
    (net (code "105") (name "Net-(L14-Pad2)") (class "Default")
      (node (ref "L14") (pin "2") (pinfunction "2_2") (pintype "passive"))
      (node (ref "R14") (pin "1") (pinfunction "1_1") (pintype "passive"))
    )
    (net (code "106") (name "Net-(L15-Pad2)") (class "Default")
      (node (ref "L15") (pin "2") (pinfunction "2_2") (pintype "passive"))
      (node (ref "R15") (pin "1") (pinfunction "1_1") (pintype "passive"))
    )
    (net (code "107") (name "Net-(L16-Pad2)") (class "Default")
      (node (ref "L16") (pin "2") (pinfunction "2_2") (pintype "passive"))
      (node (ref "R16") (pin "1") (pinfunction "1_1") (pintype "passive"))
    )
    (net (code "108") (name "Net-(PNCLED-Pad1)") (class "Default")
      (node (ref "PNCLED") (pin "1") (pinfunction "1_1") (pintype "bidirectional"))
      (node (ref "R20") (pin "2") (pinfunction "2_2") (pintype "passive"))
    )
    (net (code "109") (name "Net-(PNCSW-Pad2)") (class "Default")
      (node (ref "PNCSW") (pin "2") (pinfunction "2_2") (pintype "bidirectional"))
      (node (ref "R19") (pin "1") (pinfunction "1_1") (pintype "passive"))
    )
    (net (code "110") (name "Net-(PWRLED-Pad1)") (class "Default")
      (node (ref "PWRLED") (pin "1") (pinfunction "1_1") (pintype "bidirectional"))
      (node (ref "R21") (pin "2") (pinfunction "2_2") (pintype "passive"))
    )
    (net (code "111") (name "Net-(T1-B)") (class "Default")
      (node (ref "R18") (pin "2") (pinfunction "2_2") (pintype "passive"))
      (node (ref "T1") (pin "1") (pinfunction "B_1") (pintype "passive"))
    )
    (net (code "112") (name "Net-(T1-C)") (class "Default")
      (node (ref "R20") (pin "1") (pinfunction "1_1") (pintype "passive"))
      (node (ref "T1") (pin "3") (pinfunction "C_3") (pintype "passive"))
    )
    (net (code "113") (name "Net-(T2-B)") (class "Default")
      (node (ref "R17") (pin "2") (pinfunction "2_2") (pintype "passive"))
      (node (ref "T2") (pin "1") (pinfunction "B_1") (pintype "passive"))
    )
    (net (code "114") (name "Net-(T2-C)") (class "Default")
      (node (ref "R21") (pin "1") (pinfunction "1_1") (pintype "passive"))
      (node (ref "T2") (pin "3") (pinfunction "C_3") (pintype "passive"))
    )
    (net (code "115") (name "Net-(U1-A1)") (class "Default")
      (node (ref "D1") (pin "C") (pinfunction "C_C") (pintype "passive"))
      (node (ref "R1") (pin "2") (pinfunction "2_2") (pintype "passive"))
      (node (ref "U1") (pin "1") (pinfunction "A1_1") (pintype "passive"))
    )
    (net (code "116") (name "Net-(U1-A2)") (class "Default")
      (node (ref "D2") (pin "C") (pinfunction "C_C") (pintype "passive"))
      (node (ref "R2") (pin "2") (pinfunction "2_2") (pintype "passive"))
      (node (ref "U1") (pin "4") (pinfunction "A2_4") (pintype "passive"))
    )
    (net (code "117") (name "Net-(U1-C1)") (class "Default")
      (node (ref "D1") (pin "A") (pinfunction "A_A") (pintype "passive"))
      (node (ref "L1") (pin "2") (pinfunction "2_2") (pintype "passive"))
      (node (ref "U1") (pin "2") (pinfunction "C1_2") (pintype "passive"))
    )
    (net (code "118") (name "Net-(U1-C2)") (class "Default")
      (node (ref "D2") (pin "A") (pinfunction "A_A") (pintype "passive"))
      (node (ref "L3") (pin "2") (pinfunction "2_2") (pintype "passive"))
      (node (ref "U1") (pin "3") (pinfunction "C2_3") (pintype "passive"))
    )
    (net (code "119") (name "Net-(U2-A1)") (class "Default")
      (node (ref "D3") (pin "C") (pinfunction "C_C") (pintype "passive"))
      (node (ref "R3") (pin "2") (pinfunction "2_2") (pintype "passive"))
      (node (ref "U2") (pin "1") (pinfunction "A1_1") (pintype "passive"))
    )
    (net (code "120") (name "Net-(U2-A2)") (class "Default")
      (node (ref "D4") (pin "C") (pinfunction "C_C") (pintype "passive"))
      (node (ref "R4") (pin "2") (pinfunction "2_2") (pintype "passive"))
      (node (ref "U2") (pin "4") (pinfunction "A2_4") (pintype "passive"))
    )
    (net (code "121") (name "Net-(U2-C1)") (class "Default")
      (node (ref "D3") (pin "A") (pinfunction "A_A") (pintype "passive"))
      (node (ref "L5") (pin "2") (pinfunction "2_2") (pintype "passive"))
      (node (ref "U2") (pin "2") (pinfunction "C1_2") (pintype "passive"))
    )
    (net (code "122") (name "Net-(U2-C2)") (class "Default")
      (node (ref "D4") (pin "A") (pinfunction "A_A") (pintype "passive"))
      (node (ref "L7") (pin "2") (pinfunction "2_2") (pintype "passive"))
      (node (ref "U2") (pin "3") (pinfunction "C2_3") (pintype "passive"))
    )
    (net (code "123") (name "unconnected-(PWR-Pad1)") (class "Default")
      (node (ref "PWR") (pin "1") (pinfunction "1_1") (pintype "passive"))
    )
  )
)
